# 05_-_HDMI_INPUT.net
KiCad netlist of a schematic drawn in Altium Designer
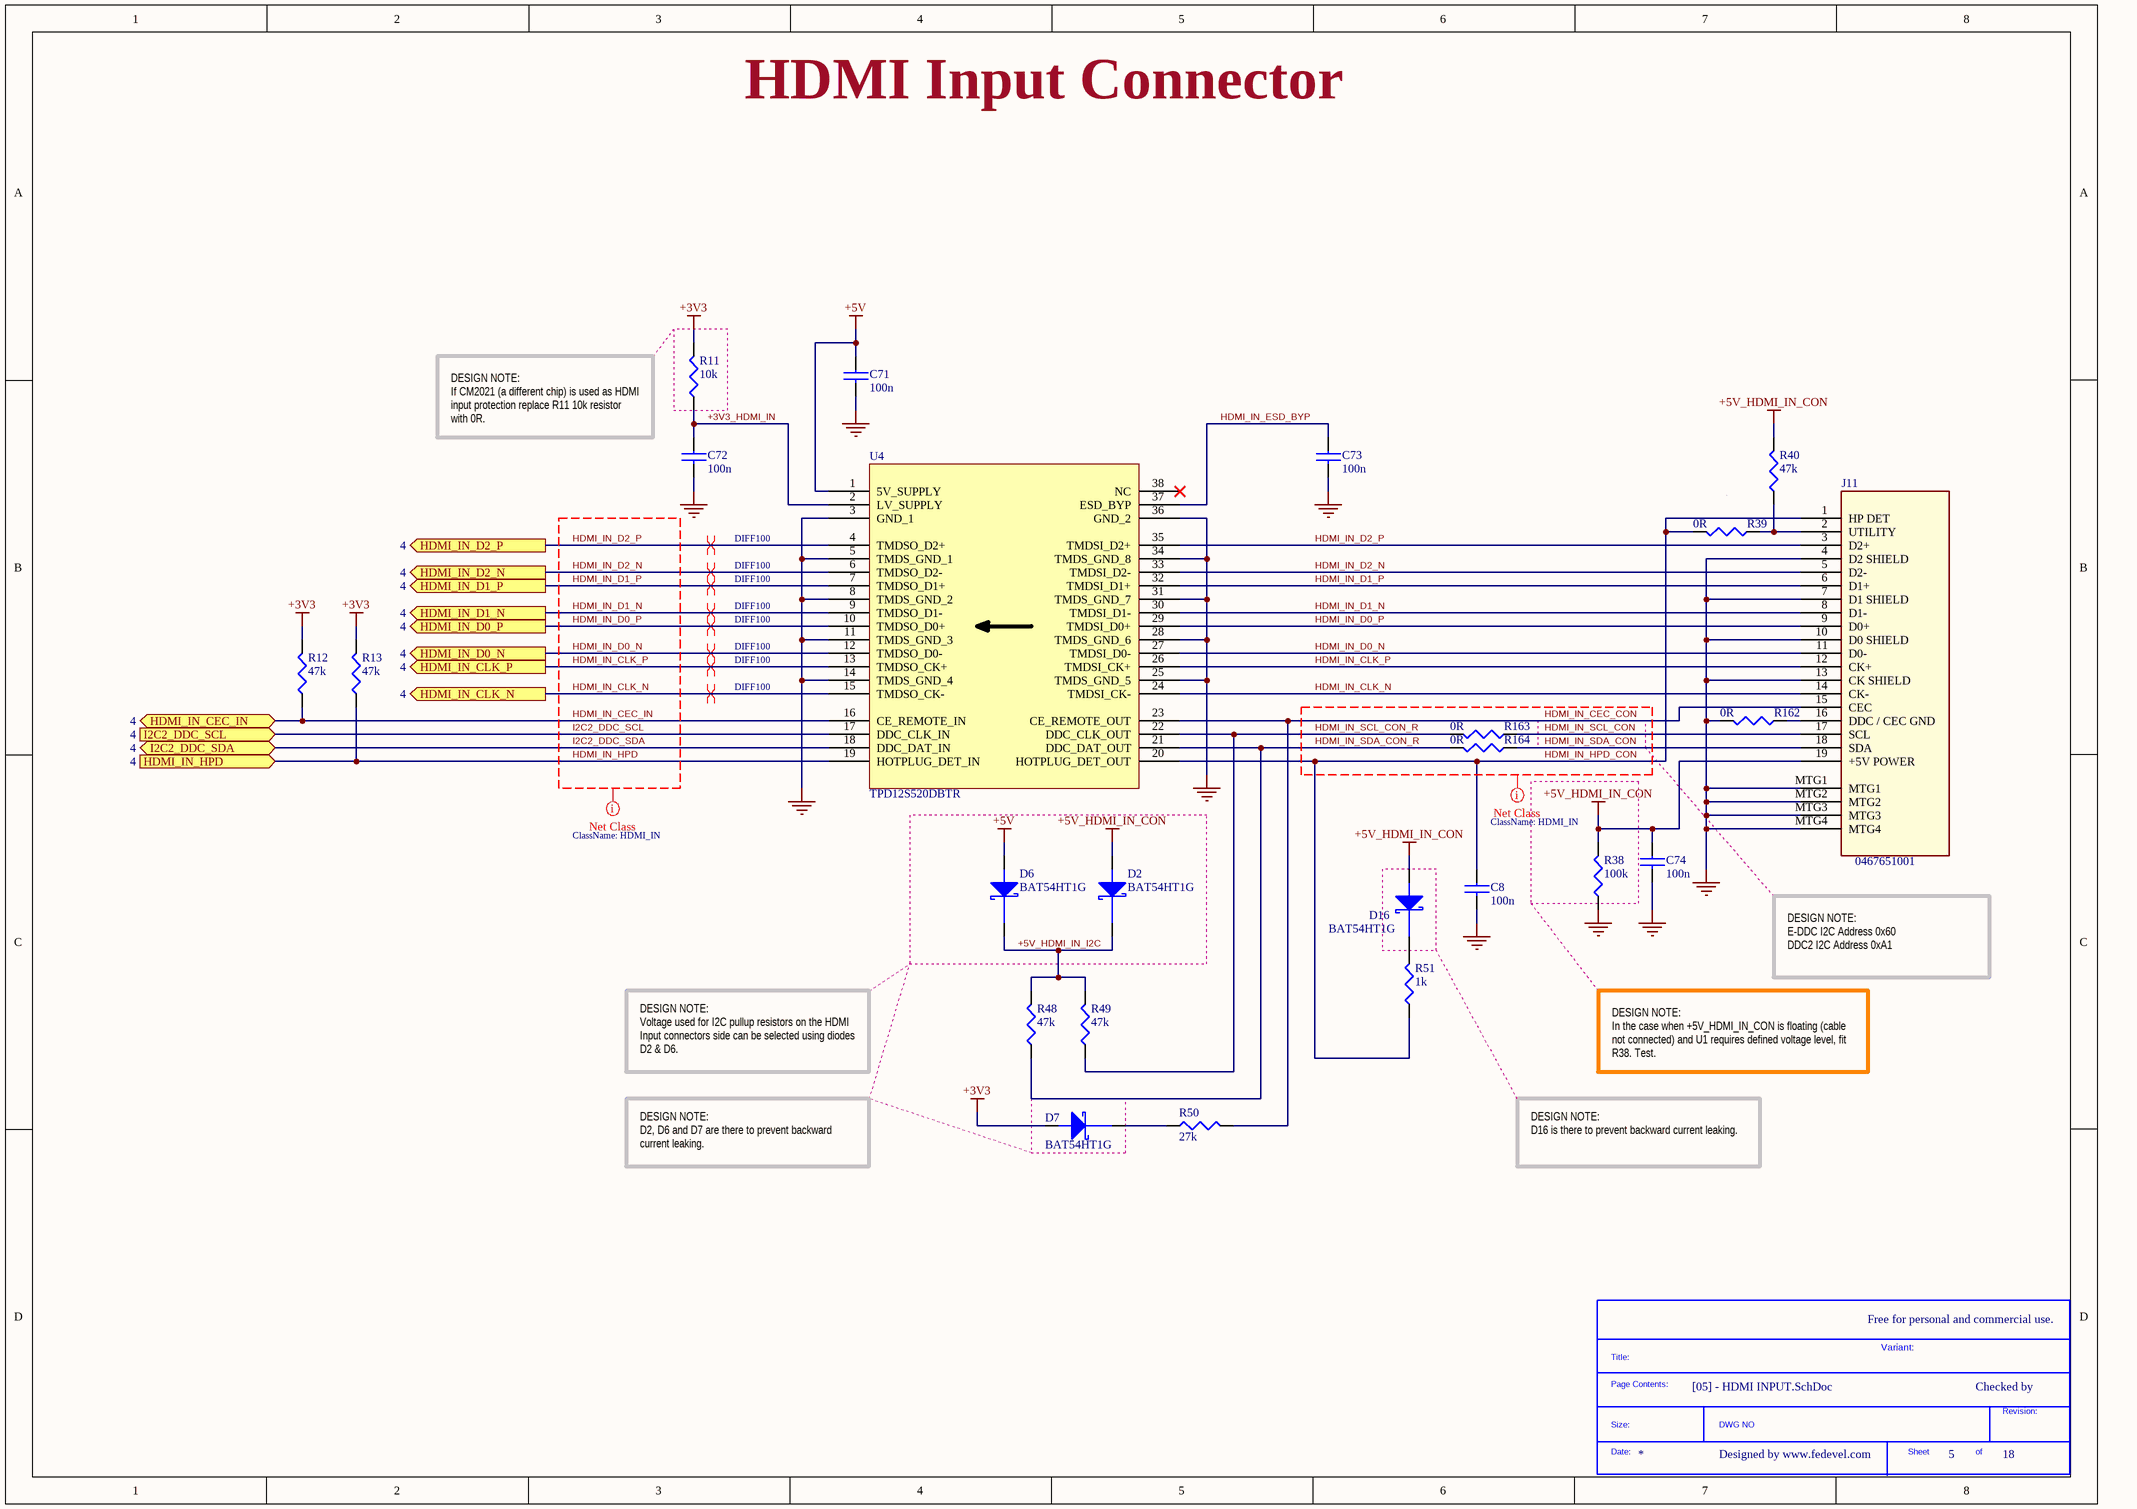
[diagram p0: [05] - HDMI INPUT.SchDoc]

(export (version "E")
  (design (tool "Eeschema 10.0.6"))
  (components
    (comp (ref "C8")
      (value "100n")
      (footprint "C0402")
      (description "CAP CER .10UF 50V X5R 10% 0402")
      (fields
        (field (name "MANUFACTURER") "TDK Corporation")
        (field (name "MANUFACTURER PART NUMBER") "C1005X5R1H104K")
      )
      (libsource (lib "Integrated_Library_FEDEVEL_APR_2015") (part "C1005X5R1H104K"))
    )
    (comp (ref "C71")
      (value "100n")
      (footprint "C0402")
      (description "CAP CER .10UF 50V X5R 10% 0402")
      (fields
        (field (name "MANUFACTURER") "TDK Corporation")
        (field (name "MANUFACTURER PART NUMBER") "C1005X5R1H104K")
      )
      (libsource (lib "Integrated_Library_FEDEVEL_APR_2015") (part "C1005X5R1H104K"))
    )
    (comp (ref "C72")
      (value "100n")
      (footprint "C0402")
      (description "CAP CER .10UF 50V X5R 10% 0402")
      (fields
        (field (name "MANUFACTURER") "TDK Corporation")
        (field (name "MANUFACTURER PART NUMBER") "C1005X5R1H104K")
      )
      (libsource (lib "Integrated_Library_FEDEVEL_APR_2015") (part "C1005X5R1H104K"))
    )
    (comp (ref "C73")
      (value "100n")
      (footprint "C0402")
      (description "CAP CER .10UF 50V X5R 10% 0402")
      (fields
        (field (name "MANUFACTURER") "TDK Corporation")
        (field (name "MANUFACTURER PART NUMBER") "C1005X5R1H104K")
      )
      (libsource (lib "Integrated_Library_FEDEVEL_APR_2015") (part "C1005X5R1H104K"))
    )
    (comp (ref "C74")
      (value "100n")
      (footprint "C0402")
      (description "CAP CER .10UF 50V X5R 10% 0402")
      (fields
        (field (name "MANUFACTURER") "TDK Corporation")
        (field (name "MANUFACTURER PART NUMBER") "C1005X5R1H104K")
      )
      (libsource (lib "Integrated_Library_FEDEVEL_APR_2015") (part "C1005X5R1H104K"))
    )
    (comp (ref "D2")
      (value "BAT54HT1G")
      (footprint "SOD323")
      (description "DIODE SCHOTTKY 30V 0.2A SOD323")
      (fields (field (name "MANUFACTURER") "Fairchild Semiconductor") (field (name ".CREATOR") "MM"))
      (libsource (lib "Integrated_Library_FEDEVEL_APR_2015") (part "BAT54HT1G"))
    )
    (comp (ref "D6")
      (value "BAT54HT1G")
      (footprint "SOD323")
      (description "DIODE SCHOTTKY 30V 0.2A SOD323")
      (fields (field (name "MANUFACTURER") "Fairchild Semiconductor") (field (name ".CREATOR") "MM"))
      (libsource (lib "Integrated_Library_FEDEVEL_APR_2015") (part "BAT54HT1G"))
    )
    (comp (ref "D7")
      (value "BAT54HT1G")
      (footprint "SOD323")
      (description "DIODE SCHOTTKY 30V 0.2A SOD323")
      (fields (field (name "MANUFACTURER") "Fairchild Semiconductor") (field (name ".CREATOR") "MM"))
      (libsource (lib "Integrated_Library_FEDEVEL_APR_2015") (part "BAT54HT1G"))
    )
    (comp (ref "D16")
      (value "BAT54HT1G")
      (footprint "SOD323")
      (description "DIODE SCHOTTKY 30V 0.2A SOD323")
      (fields (field (name "MANUFACTURER") "Fairchild Semiconductor") (field (name ".CREATOR") "MM"))
      (libsource (lib "Integrated_Library_FEDEVEL_APR_2015") (part "BAT54HT1G"))
    )
    (comp (ref "J11")
      (value "0467651001")
      (footprint "Micro_HDMI")
      (description "CONN RCPT HDMI MICRO TYPE-D R/A")
      (fields
        (field (name "MANUFACTURER") "Molex Inc")
        (field (name ".CREATOR") "MM")
        (field (name ".CHECKED PCB") "MM, paper model not checked")
        (field (name ".CHECKED SCH") "MM")
      )
      (libsource (lib "Integrated_Library_FEDEVEL_APR_2015") (part "0467651001"))
    )
    (comp (ref "R11")
      (value "10k")
      (footprint "R0402")
      (description "RES 10.0K OHM 1/16W 1% 0402 SMD")
      (fields
        (field (name "MANUFACTURER") "Yageo")
        (field (name "MANUFACTURER PART NUMBER") "RC0402FR-0710KL")
      )
      (libsource (lib "Integrated_Library_FEDEVEL_APR_2015") (part "RC0402FR-0710KL"))
    )
    (comp (ref "R12")
      (value "47k")
      (footprint "R0402")
      (description "RES 47.0K OHM 1/16W 1% 0402 SMD")
      (fields
        (field (name "MANUFACTURER") "Yageo")
        (field (name "MANUFACTURER PART NUMBER") "RC0402FR-0747KL")
      )
      (libsource (lib "Integrated_Library_FEDEVEL_APR_2015") (part "RC0402FR-0747KL"))
    )
    (comp (ref "R13")
      (value "47k")
      (footprint "R0402")
      (description "RES 47.0K OHM 1/16W 1% 0402 SMD")
      (fields
        (field (name "MANUFACTURER") "Yageo")
        (field (name "MANUFACTURER PART NUMBER") "RC0402FR-0747KL")
      )
      (libsource (lib "Integrated_Library_FEDEVEL_APR_2015") (part "RC0402FR-0747KL"))
    )
    (comp (ref "R38")
      (value "100k")
      (footprint "R0402")
      (description "RES 100K OHM 1/16W 1% 0402 SMD")
      (fields
        (field (name "MANUFACTURER") "Stackpole Electronics Inc")
        (field (name "MANUFACTURER PART NUMBER") "RMCF0402FT100K")
      )
      (libsource (lib "Integrated_Library_FEDEVEL_APR_2015") (part "RMCF0402FT100K"))
    )
    (comp (ref "R39")
      (value "0R")
      (footprint "R0402")
      (description "RES 0.0 OHM 1/16W 0402 SMD")
      (fields
        (field (name "MANUFACTURER") "Yageo")
        (field (name "MANUFACTURER PART NUMBER") "RC0402JR-070RL")
      )
      (libsource (lib "Integrated_Library_FEDEVEL_APR_2015") (part "RC0402JR-070RL"))
    )
    (comp (ref "R40")
      (value "47k")
      (footprint "R0402")
      (description "RES 47.0K OHM 1/16W 1% 0402 SMD")
      (fields
        (field (name "MANUFACTURER") "Yageo")
        (field (name "MANUFACTURER PART NUMBER") "RC0402FR-0747KL")
      )
      (libsource (lib "Integrated_Library_FEDEVEL_APR_2015") (part "RC0402FR-0747KL"))
    )
    (comp (ref "R48")
      (value "47k")
      (footprint "R0402")
      (description "RES 47.0K OHM 1/16W 1% 0402 SMD")
      (fields
        (field (name "MANUFACTURER") "Yageo")
        (field (name "MANUFACTURER PART NUMBER") "RC0402FR-0747KL")
      )
      (libsource (lib "Integrated_Library_FEDEVEL_APR_2015") (part "RC0402FR-0747KL"))
    )
    (comp (ref "R49")
      (value "47k")
      (footprint "R0402")
      (description "RES 47.0K OHM 1/16W 1% 0402 SMD")
      (fields
        (field (name "MANUFACTURER") "Yageo")
        (field (name "MANUFACTURER PART NUMBER") "RC0402FR-0747KL")
      )
      (libsource (lib "Integrated_Library_FEDEVEL_APR_2015") (part "RC0402FR-0747KL"))
    )
    (comp (ref "R50")
      (value "27k")
      (footprint "R0402")
      (description "RES 27.0K OHM 1/16W 1% 0402 SMD")
      (fields
        (field (name "MANUFACTURER") "Yageo")
        (field (name "MANUFACTURER PART NUMBER") "RC0402FR-0727KL")
      )
      (libsource (lib "Integrated_Library_FEDEVEL_APR_2015") (part "RC0402FR-0727KL"))
    )
    (comp (ref "R51")
      (value "1k")
      (footprint "R0402")
      (description "RES 1.00K OHM 1/16W 1% 0402 SMD")
      (fields
        (field (name "MANUFACTURER") "Yageo")
        (field (name "MANUFACTURER PART NUMBER") "RC0402FR-071KL")
      )
      (libsource (lib "Integrated_Library_FEDEVEL_APR_2015") (part "RC0402FR-071KL"))
    )
    (comp (ref "R162")
      (value "0R")
      (footprint "R0402")
      (description "RES 0.0 OHM 1/16W 0402 SMD")
      (fields
        (field (name "MANUFACTURER") "Yageo")
        (field (name "MANUFACTURER PART NUMBER") "RC0402JR-070RL")
      )
      (libsource (lib "Integrated_Library_FEDEVEL_APR_2015") (part "RC0402JR-070RL"))
    )
    (comp (ref "R163")
      (value "0R")
      (footprint "R0402")
      (description "RES 0.0 OHM 1/16W 0402 SMD")
      (fields
        (field (name "MANUFACTURER") "Yageo")
        (field (name "MANUFACTURER PART NUMBER") "RC0402JR-070RL")
      )
      (libsource (lib "Integrated_Library_FEDEVEL_APR_2015") (part "RC0402JR-070RL"))
    )
    (comp (ref "R164")
      (value "0R")
      (footprint "R0402")
      (description "RES 0.0 OHM 1/16W 0402 SMD")
      (fields
        (field (name "MANUFACTURER") "Yageo")
        (field (name "MANUFACTURER PART NUMBER") "RC0402JR-070RL")
      )
      (libsource (lib "Integrated_Library_FEDEVEL_APR_2015") (part "RC0402JR-070RL"))
    )
    (comp (ref "U4")
      (value "TPD12S520DBTR")
      (footprint "TSSOP_38")
      (description "IC HDMI RCVR PORT PROT 38-TSSOP")
      (fields
        (field (name "MANUFACTURER") "Texas Instruments")
        (field (name ".CREATOR") "MM")
        (field (name ".CHECKED PCB") "MM")
        (field (name ".CHECKED SCH") "MM")
      )
      (libsource (lib "Integrated_Library_FEDEVEL_APR_2015") (part "TPD12S520DBTR"))
    )
  )
  (nets
    (net (code "1") (name "+3V3") (class "Default")
      (node (ref "D7") (pin "2") (pinfunction "Anode_2") (pintype "passive"))
      (node (ref "R11") (pin "2") (pinfunction "2_2") (pintype "passive"))
      (node (ref "R12") (pin "2") (pinfunction "2_2") (pintype "passive"))
      (node (ref "R13") (pin "2") (pinfunction "2_2") (pintype "passive"))
    )
    (net (code "2") (name "+5V") (class "Default")
      (node (ref "C71") (pin "1") (pinfunction "1_1") (pintype "passive"))
      (node (ref "D6") (pin "2") (pinfunction "Anode_2") (pintype "passive"))
      (node (ref "U4") (pin "1") (pinfunction "5V_SUPPLY_1") (pintype "passive"))
    )
    (net (code "3") (name "+5V_HDMI_IN_CON") (class "Default")
      (node (ref "C74") (pin "1") (pinfunction "1_1") (pintype "passive"))
      (node (ref "D16") (pin "2") (pinfunction "Anode_2") (pintype "passive"))
      (node (ref "D2") (pin "2") (pinfunction "Anode_2") (pintype "passive"))
      (node (ref "J11") (pin "19") (pinfunction "+5V_POWER_19") (pintype "passive"))
      (node (ref "R38") (pin "2") (pinfunction "2_2") (pintype "passive"))
      (node (ref "R40") (pin "2") (pinfunction "2_2") (pintype "passive"))
    )
    (net (code "4") (name "/+3V3_HDMI_IN") (class "Default")
      (node (ref "C72") (pin "1") (pinfunction "1_1") (pintype "passive"))
      (node (ref "R11") (pin "1") (pinfunction "1_1") (pintype "passive"))
      (node (ref "U4") (pin "2") (pinfunction "LV_SUPPLY_2") (pintype "passive"))
    )
    (net (code "5") (name "/+5V_HDMI_IN_I2C") (class "Default")
      (node (ref "D2") (pin "1") (pinfunction "Cathode_1") (pintype "passive"))
      (node (ref "D6") (pin "1") (pinfunction "Cathode_1") (pintype "passive"))
      (node (ref "R48") (pin "2") (pinfunction "2_2") (pintype "passive"))
      (node (ref "R49") (pin "2") (pinfunction "2_2") (pintype "passive"))
    )
    (net (code "6") (name "/HDMI_IN_CEC_CON") (class "Default")
      (node (ref "J11") (pin "15") (pinfunction "CEC_15") (pintype "passive"))
      (node (ref "R50") (pin "2") (pinfunction "2_2") (pintype "passive"))
      (node (ref "U4") (pin "23") (pinfunction "CE_REMOTE_OUT_23") (pintype "passive"))
    )
    (net (code "7") (name "/HDMI_IN_CEC_IN") (class "Default")
      (node (ref "R12") (pin "1") (pinfunction "1_1") (pintype "passive"))
      (node (ref "U4") (pin "16") (pinfunction "CE_REMOTE_IN_16") (pintype "passive"))
    )
    (net (code "8") (name "/HDMI_IN_CLK_N") (class "Default")
      (node (ref "J11") (pin "14") (pinfunction "CK-_14") (pintype "passive"))
      (node (ref "U4") (pin "15") (pinfunction "TMDSO_CK-_15") (pintype "passive"))
      (node (ref "U4") (pin "24") (pinfunction "TMDSI_CK-_24") (pintype "passive"))
    )
    (net (code "9") (name "/HDMI_IN_CLK_P") (class "Default")
      (node (ref "J11") (pin "12") (pinfunction "CK+_12") (pintype "passive"))
      (node (ref "U4") (pin "13") (pinfunction "TMDSO_CK+_13") (pintype "passive"))
      (node (ref "U4") (pin "26") (pinfunction "TMDSI_CK+_26") (pintype "passive"))
    )
    (net (code "10") (name "/HDMI_IN_D0_N") (class "Default")
      (node (ref "J11") (pin "11") (pinfunction "D0-_11") (pintype "passive"))
      (node (ref "U4") (pin "12") (pinfunction "TMDSO_D0-_12") (pintype "passive"))
      (node (ref "U4") (pin "27") (pinfunction "TMDSI_D0-_27") (pintype "passive"))
    )
    (net (code "11") (name "/HDMI_IN_D0_P") (class "Default")
      (node (ref "J11") (pin "9") (pinfunction "D0+_9") (pintype "passive"))
      (node (ref "U4") (pin "10") (pinfunction "TMDSO_D0+_10") (pintype "passive"))
      (node (ref "U4") (pin "29") (pinfunction "TMDSI_D0+_29") (pintype "passive"))
    )
    (net (code "12") (name "/HDMI_IN_D1_N") (class "Default")
      (node (ref "J11") (pin "8") (pinfunction "D1-_8") (pintype "passive"))
      (node (ref "U4") (pin "30") (pinfunction "TMDSI_D1-_30") (pintype "passive"))
      (node (ref "U4") (pin "9") (pinfunction "TMDSO_D1-_9") (pintype "passive"))
    )
    (net (code "13") (name "/HDMI_IN_D1_P") (class "Default")
      (node (ref "J11") (pin "6") (pinfunction "D1+_6") (pintype "passive"))
      (node (ref "U4") (pin "32") (pinfunction "TMDSI_D1+_32") (pintype "passive"))
      (node (ref "U4") (pin "7") (pinfunction "TMDSO_D1+_7") (pintype "passive"))
    )
    (net (code "14") (name "/HDMI_IN_D2_N") (class "Default")
      (node (ref "J11") (pin "5") (pinfunction "D2-_5") (pintype "passive"))
      (node (ref "U4") (pin "33") (pinfunction "TMDSI_D2-_33") (pintype "passive"))
      (node (ref "U4") (pin "6") (pinfunction "TMDSO_D2-_6") (pintype "passive"))
    )
    (net (code "15") (name "/HDMI_IN_D2_P") (class "Default")
      (node (ref "J11") (pin "3") (pinfunction "D2+_3") (pintype "passive"))
      (node (ref "U4") (pin "35") (pinfunction "TMDSI_D2+_35") (pintype "passive"))
      (node (ref "U4") (pin "4") (pinfunction "TMDSO_D2+_4") (pintype "passive"))
    )
    (net (code "16") (name "/HDMI_IN_ESD_BYP") (class "Default")
      (node (ref "C73") (pin "1") (pinfunction "1_1") (pintype "passive"))
      (node (ref "U4") (pin "37") (pinfunction "ESD_BYP_37") (pintype "passive"))
    )
    (net (code "17") (name "/HDMI_IN_HPD") (class "Default")
      (node (ref "R13") (pin "1") (pinfunction "1_1") (pintype "passive"))
      (node (ref "U4") (pin "19") (pinfunction "HOTPLUG_DET_IN_19") (pintype "passive"))
    )
    (net (code "18") (name "/HDMI_IN_HPD_CON") (class "Default")
      (node (ref "C8") (pin "1") (pinfunction "1_1") (pintype "passive"))
      (node (ref "J11") (pin "1") (pinfunction "HP_DET_1") (pintype "passive"))
      (node (ref "R39") (pin "2") (pinfunction "2_2") (pintype "passive"))
      (node (ref "R51") (pin "1") (pinfunction "1_1") (pintype "passive"))
      (node (ref "U4") (pin "20") (pinfunction "HOTPLUG_DET_OUT_20") (pintype "passive"))
    )
    (net (code "19") (name "/HDMI_IN_SCL_CON") (class "Default")
      (node (ref "J11") (pin "17") (pinfunction "SCL_17") (pintype "passive"))
      (node (ref "R163") (pin "1") (pinfunction "1_1") (pintype "passive"))
    )
    (net (code "20") (name "/HDMI_IN_SCL_CON_R") (class "Default")
      (node (ref "R163") (pin "2") (pinfunction "2_2") (pintype "passive"))
      (node (ref "R49") (pin "1") (pinfunction "1_1") (pintype "passive"))
      (node (ref "U4") (pin "22") (pinfunction "DDC_CLK_OUT_22") (pintype "passive"))
    )
    (net (code "21") (name "/HDMI_IN_SDA_CON") (class "Default")
      (node (ref "J11") (pin "18") (pinfunction "SDA_18") (pintype "passive"))
      (node (ref "R164") (pin "1") (pinfunction "1_1") (pintype "passive"))
    )
    (net (code "22") (name "/HDMI_IN_SDA_CON_R") (class "Default")
      (node (ref "R164") (pin "2") (pinfunction "2_2") (pintype "passive"))
      (node (ref "R48") (pin "1") (pinfunction "1_1") (pintype "passive"))
      (node (ref "U4") (pin "21") (pinfunction "DDC_DAT_OUT_21") (pintype "passive"))
    )
    (net (code "23") (name "/I2C2_DDC_SCL") (class "Default")
      (node (ref "U4") (pin "17") (pinfunction "DDC_CLK_IN_17") (pintype "passive"))
    )
    (net (code "24") (name "/I2C2_DDC_SDA") (class "Default")
      (node (ref "U4") (pin "18") (pinfunction "DDC_DAT_IN_18") (pintype "passive"))
    )
    (net (code "25") (name "GND") (class "Default")
      (node (ref "C71") (pin "2") (pinfunction "2_2") (pintype "passive"))
      (node (ref "C72") (pin "2") (pinfunction "2_2") (pintype "passive"))
      (node (ref "C73") (pin "2") (pinfunction "2_2") (pintype "passive"))
      (node (ref "C74") (pin "2") (pinfunction "2_2") (pintype "passive"))
      (node (ref "C8") (pin "2") (pinfunction "2_2") (pintype "passive"))
      (node (ref "J11") (pin "10") (pinfunction "D0_SHIELD_10") (pintype "passive"))
      (node (ref "J11") (pin "13") (pinfunction "CK_SHIELD_13") (pintype "passive"))
      (node (ref "J11") (pin "4") (pinfunction "D2_SHIELD_4") (pintype "passive"))
      (node (ref "J11") (pin "7") (pinfunction "D1_SHIELD_7") (pintype "passive"))
      (node (ref "J11") (pin "MTG1") (pinfunction "MTG1_MTG1") (pintype "passive"))
      (node (ref "J11") (pin "MTG2") (pinfunction "MTG2_MTG2") (pintype "passive"))
      (node (ref "J11") (pin "MTG3") (pinfunction "MTG3_MTG3") (pintype "passive"))
      (node (ref "J11") (pin "MTG4") (pinfunction "MTG4_MTG4") (pintype "passive"))
      (node (ref "R162") (pin "2") (pinfunction "2_2") (pintype "passive"))
      (node (ref "R38") (pin "1") (pinfunction "1_1") (pintype "passive"))
      (node (ref "U4") (pin "11") (pinfunction "TMDS_GND_3_11") (pintype "passive"))
      (node (ref "U4") (pin "14") (pinfunction "TMDS_GND_4_14") (pintype "passive"))
      (node (ref "U4") (pin "25") (pinfunction "TMDS_GND_5_25") (pintype "passive"))
      (node (ref "U4") (pin "28") (pinfunction "TMDS_GND_6_28") (pintype "passive"))
      (node (ref "U4") (pin "3") (pinfunction "GND_1_3") (pintype "passive"))
      (node (ref "U4") (pin "31") (pinfunction "TMDS_GND_7_31") (pintype "passive"))
      (node (ref "U4") (pin "34") (pinfunction "TMDS_GND_8_34") (pintype "passive"))
      (node (ref "U4") (pin "36") (pinfunction "GND_2_36") (pintype "passive"))
      (node (ref "U4") (pin "5") (pinfunction "TMDS_GND_1_5") (pintype "passive"))
      (node (ref "U4") (pin "8") (pinfunction "TMDS_GND_2_8") (pintype "passive"))
    )
    (net (code "26") (name "Net-(D7-Cathode)") (class "Default")
      (node (ref "D7") (pin "1") (pinfunction "Cathode_1") (pintype "passive"))
      (node (ref "R50") (pin "1") (pinfunction "1_1") (pintype "passive"))
    )
    (net (code "27") (name "Net-(D16-Cathode)") (class "Default")
      (node (ref "D16") (pin "1") (pinfunction "Cathode_1") (pintype "passive"))
      (node (ref "R51") (pin "2") (pinfunction "2_2") (pintype "passive"))
    )
    (net (code "28") (name "Net-(J11-DDC_{slash}_CEC_GND)") (class "Default")
      (node (ref "J11") (pin "16") (pinfunction "DDC_/_CEC_GND_16") (pintype "passive"))
      (node (ref "R162") (pin "1") (pinfunction "1_1") (pintype "passive"))
    )
    (net (code "29") (name "Net-(J11-UTILITY)") (class "Default")
      (node (ref "J11") (pin "2") (pinfunction "UTILITY_2") (pintype "passive"))
      (node (ref "R39") (pin "1") (pinfunction "1_1") (pintype "passive"))
      (node (ref "R40") (pin "1") (pinfunction "1_1") (pintype "passive"))
    )
    (net (code "30") (name "unconnected-(U4-NC-Pad38)") (class "Default")
      (node (ref "U4") (pin "38") (pinfunction "NC_38") (pintype "passive+no_connect"))
    )
  )
)
